# PIC32_WIZ810MJ.net
KiCad netlist of a schematic drawn in EAGLE
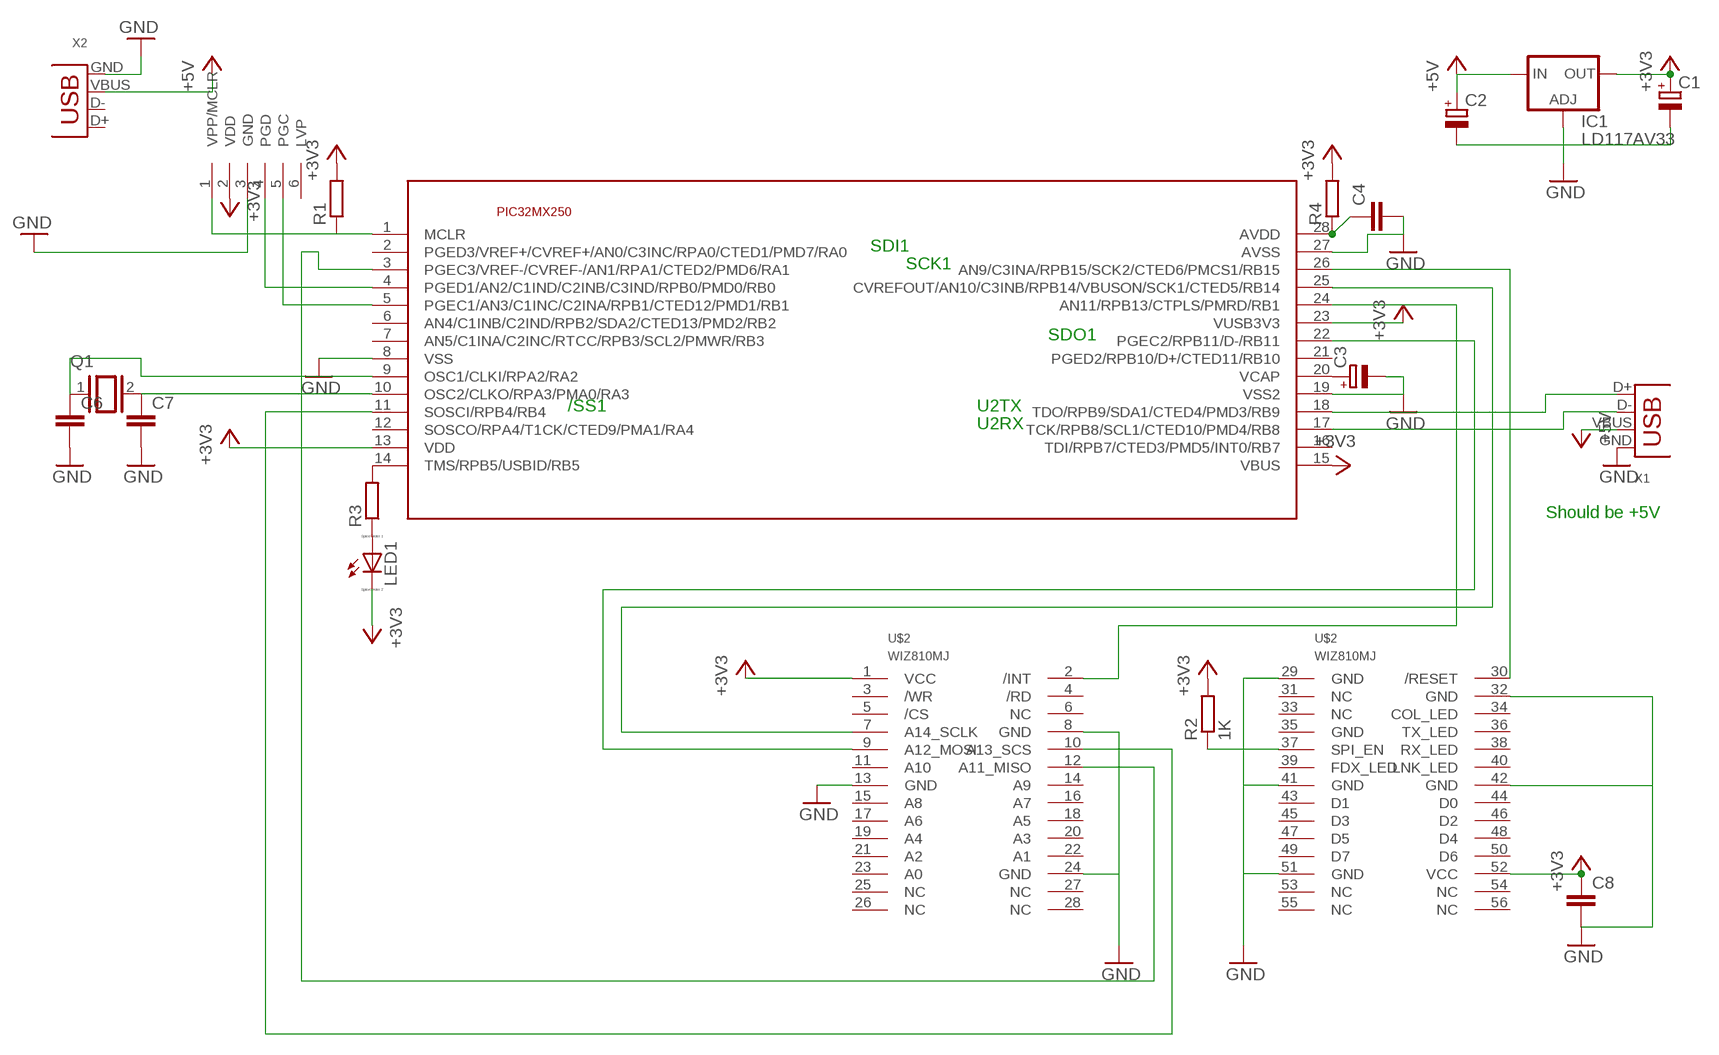
[diagram p0: schematic, sheet 1]

(export (version "E")
  (design (tool "Eeschema 10.0.6"))
  (components
    (comp (ref "C1")
      (value "CPOL-EUE3.5-10")
      (footprint "eagle-import:E3,5-10")
      (libsource (lib "eagle-import") (part "CPOL-EUE3.5-10"))
    )
    (comp (ref "C2")
      (value "CPOL-EUE3.5-10")
      (footprint "eagle-import:E3,5-10")
      (libsource (lib "eagle-import") (part "CPOL-EUE3.5-10"))
    )
    (comp (ref "C3")
      (value "CPOL-EUE2.5-6")
      (footprint "eagle-import:E2,5-6")
      (libsource (lib "eagle-import") (part "CPOL-EUE2.5-6"))
    )
    (comp (ref "C4")
      (value "C-EU050-055X075")
      (footprint "eagle-import:C050-055X075")
      (libsource (lib "eagle-import") (part "C-EU050-055X075"))
    )
    (comp (ref "C6")
      (value "C-EU025-025X050")
      (footprint "eagle-import:C025-025X050")
      (libsource (lib "eagle-import") (part "C-EU025-025X050"))
    )
    (comp (ref "C7")
      (value "C-EU025-025X050")
      (footprint "eagle-import:C025-025X050")
      (libsource (lib "eagle-import") (part "C-EU025-025X050"))
    )
    (comp (ref "C8")
      (value "C-EU050-055X075")
      (footprint "eagle-import:C050-055X075")
      (libsource (lib "eagle-import") (part "C-EU050-055X075"))
    )
    (comp (ref "IC1")
      (value "LD117AV33")
      (footprint "eagle-import:TO220L1")
      (libsource (lib "eagle-import") (part "LD117A?V33"))
    )
    (comp (ref "LED1")
      (value "LED_ELD260")
      (footprint "eagle-import:LED_LD260")
      (libsource (lib "eagle-import") (part "LED_ELD260"))
    )
    (comp (ref "Q1")
      (value "XTAL/S")
      (footprint "eagle-import:QS")
      (libsource (lib "eagle-import") (part "XTAL/S"))
    )
    (comp (ref "R1")
      (value "R-EU_0204/5")
      (footprint "eagle-import:0204_5")
      (libsource (lib "eagle-import") (part "R-EU_0204/5"))
    )
    (comp (ref "R2")
      (value "1K")
      (footprint "eagle-import:0204_5")
      (libsource (lib "eagle-import") (part "R-EU_0204/5"))
    )
    (comp (ref "R3")
      (value "R-EU_0204/5")
      (footprint "eagle-import:0204_5")
      (libsource (lib "eagle-import") (part "R-EU_0204/5"))
    )
    (comp (ref "R4")
      (value "R-EU_0204/5")
      (footprint "eagle-import:0204_5")
      (libsource (lib "eagle-import") (part "R-EU_0204/5"))
    )
    (comp (ref "U$1")
      (value "PIC32MX2XXDIP28_SLIM")
      (footprint "eagle-import:DIP254P762X508-28")
      (libsource (lib "eagle-import") (part "PIC32MX2XXDIP28_SLIM"))
    )
    (comp (ref "U$2")
      (value "WIZ810MJ")
      (footprint "eagle-import:WIZ810MJ")
      (libsource (lib "eagle-import") (part "WIZ810MJ"))
    )
    (comp (ref "U$3")
      (value "ICSP-6_6P")
      (footprint "eagle-import:1X06-CLEANBIG")
      (libsource (lib "eagle-import") (part "ICSP-6_6P"))
    )
    (comp (ref "X1")
      (value "USB-A-H")
      (footprint "eagle-import:USB-A-H")
      (libsource (lib "eagle-import") (part "USB-A-H"))
    )
    (comp (ref "X2")
      (value "USB-B-H")
      (footprint "eagle-import:USB-B-H")
      (libsource (lib "eagle-import") (part "USB-B-H"))
    )
  )
  (nets
    (net (code "1") (name "+3V3") (class "Default")
      (node (ref "C1") (pin "+") (pinfunction "+_+") (pintype "passive"))
      (node (ref "C8") (pin "1") (pinfunction "1_1") (pintype "passive"))
      (node (ref "IC1") (pin "2") (pinfunction "OUT_2") (pintype "passive"))
      (node (ref "LED1") (pin "K") (pinfunction "C_K") (pintype "passive"))
      (node (ref "R1") (pin "2") (pinfunction "2_2") (pintype "passive"))
      (node (ref "R2") (pin "2") (pinfunction "2_2") (pintype "passive"))
      (node (ref "R4") (pin "2") (pinfunction "2_2") (pintype "passive"))
      (node (ref "U$1") (pin "13") (pinfunction "VDD_13") (pintype "power_in"))
      (node (ref "U$1") (pin "15") (pinfunction "VBUS_15") (pintype "bidirectional"))
      (node (ref "U$1") (pin "23") (pinfunction "VUSB3V3_23") (pintype "bidirectional"))
      (node (ref "U$2") (pin "1") (pinfunction "VCC_1") (pintype "bidirectional"))
      (node (ref "U$2") (pin "52") (pinfunction "VCC_52") (pintype "bidirectional"))
      (node (ref "U$3") (pin "2") (pinfunction "VDD_2") (pintype "bidirectional"))
    )
    (net (code "2") (name "+5V") (class "Default")
      (node (ref "C2") (pin "+") (pinfunction "+_+") (pintype "passive"))
      (node (ref "IC1") (pin "3") (pinfunction "IN_3") (pintype "input"))
      (node (ref "X1") (pin "VBUS") (pinfunction "VBUS_VBUS") (pintype "bidirectional"))
      (node (ref "X2") (pin "VBUS") (pinfunction "VBUS_VBUS") (pintype "bidirectional"))
    )
    (net (code "3") (name "GND") (class "Default")
      (node (ref "C1") (pin "-") (pinfunction "-_-") (pintype "passive"))
      (node (ref "C2") (pin "-") (pinfunction "-_-") (pintype "passive"))
      (node (ref "C3") (pin "-") (pinfunction "-_-") (pintype "passive"))
      (node (ref "C4") (pin "2") (pinfunction "2_2") (pintype "passive"))
      (node (ref "C6") (pin "2") (pinfunction "2_2") (pintype "passive"))
      (node (ref "C7") (pin "2") (pinfunction "2_2") (pintype "passive"))
      (node (ref "C8") (pin "2") (pinfunction "2_2") (pintype "passive"))
      (node (ref "IC1") (pin "1") (pinfunction "ADJ_1") (pintype "input"))
      (node (ref "U$1") (pin "19") (pinfunction "VSS2_19") (pintype "bidirectional"))
      (node (ref "U$1") (pin "27") (pinfunction "AVSS_27") (pintype "bidirectional"))
      (node (ref "U$1") (pin "8") (pinfunction "VSS_8") (pintype "power_in"))
      (node (ref "U$2") (pin "13") (pinfunction "GND_13") (pintype "bidirectional"))
      (node (ref "U$2") (pin "24") (pinfunction "GND_24") (pintype "bidirectional"))
      (node (ref "U$2") (pin "29") (pinfunction "GND_29") (pintype "bidirectional"))
      (node (ref "U$2") (pin "32") (pinfunction "GND_32") (pintype "bidirectional"))
      (node (ref "U$2") (pin "41") (pinfunction "GND_41") (pintype "bidirectional"))
      (node (ref "U$2") (pin "42") (pinfunction "GND_42") (pintype "bidirectional"))
      (node (ref "U$2") (pin "51") (pinfunction "GND_51") (pintype "bidirectional"))
      (node (ref "U$2") (pin "8") (pinfunction "GND_8") (pintype "bidirectional"))
      (node (ref "U$3") (pin "3") (pinfunction "GND_3") (pintype "bidirectional"))
      (node (ref "X1") (pin "GND") (pinfunction "GND_GND") (pintype "bidirectional"))
      (node (ref "X2") (pin "GND") (pinfunction "GND_GND") (pintype "bidirectional"))
    )
    (net (code "4") (name "Net-(LED1-PadA)") (class "Default")
      (node (ref "LED1") (pin "A") (pinfunction "A_A") (pintype "passive"))
      (node (ref "R3") (pin "1") (pinfunction "1_1") (pintype "passive"))
    )
    (net (code "5") (name "Net-(U$1-AN9{slash}C3INA{slash}RPB15{slash}SCK2{slash}CTED6{slash}PMCS1{slash}RB15)") (class "Default")
      (node (ref "U$1") (pin "26") (pinfunction "AN9/C3INA/RPB15/SCK2/CTED6/PMCS1/RB15_26") (pintype "bidirectional"))
      (node (ref "U$2") (pin "30") (pinfunction "/RESET_30") (pintype "bidirectional"))
    )
    (net (code "6") (name "Net-(U$1-AN11{slash}RPB13{slash}CTPLS{slash}PMRD{slash}RB1)") (class "Default")
      (node (ref "U$1") (pin "24") (pinfunction "AN11/RPB13/CTPLS/PMRD/RB1_24") (pintype "bidirectional"))
      (node (ref "U$2") (pin "2") (pinfunction "/INT_2") (pintype "bidirectional"))
    )
    (net (code "7") (name "Net-(U$1-AVDD)") (class "Default")
      (node (ref "C4") (pin "1") (pinfunction "1_1") (pintype "passive"))
      (node (ref "R4") (pin "1") (pinfunction "1_1") (pintype "passive"))
      (node (ref "U$1") (pin "28") (pinfunction "AVDD_28") (pintype "bidirectional"))
    )
    (net (code "8") (name "Net-(U$1-CVREFOUT{slash}AN10{slash}C3INB{slash}RPB14{slash}VBUSON{slash}SCK1{slash}CTED5{slash}RB14)") (class "Default")
      (node (ref "U$1") (pin "25") (pinfunction "CVREFOUT/AN10/C3INB/RPB14/VBUSON/SCK1/CTED5/RB14_25") (pintype "bidirectional"))
      (node (ref "U$2") (pin "7") (pinfunction "A14_SCLK_7") (pintype "bidirectional"))
    )
    (net (code "9") (name "Net-(U$1-MCLR)") (class "Default")
      (node (ref "R1") (pin "1") (pinfunction "1_1") (pintype "passive"))
      (node (ref "U$1") (pin "1") (pinfunction "MCLR_1") (pintype "bidirectional"))
      (node (ref "U$3") (pin "1") (pinfunction "VPP/MCLR_1") (pintype "bidirectional"))
    )
    (net (code "10") (name "Net-(U$1-OSC1{slash}CLKI{slash}RPA2{slash}RA2)") (class "Default")
      (node (ref "C6") (pin "1") (pinfunction "1_1") (pintype "passive"))
      (node (ref "Q1") (pin "1") (pinfunction "1_1") (pintype "passive"))
      (node (ref "U$1") (pin "9") (pinfunction "OSC1/CLKI/RPA2/RA2_9") (pintype "bidirectional"))
    )
    (net (code "11") (name "Net-(U$1-OSC2{slash}CLKO{slash}RPA3{slash}PMA0{slash}RA3)") (class "Default")
      (node (ref "C7") (pin "1") (pinfunction "1_1") (pintype "passive"))
      (node (ref "Q1") (pin "2") (pinfunction "2_2") (pintype "passive"))
      (node (ref "U$1") (pin "10") (pinfunction "OSC2/CLKO/RPA3/PMA0/RA3_10") (pintype "bidirectional"))
    )
    (net (code "12") (name "Net-(U$1-PGEC1{slash}AN3{slash}C1INC{slash}C2INA{slash}RPB1{slash}CTED12{slash}PMD1{slash}RB1)") (class "Default")
      (node (ref "U$1") (pin "5") (pinfunction "PGEC1/AN3/C1INC/C2INA/RPB1/CTED12/PMD1/RB1_5") (pintype "bidirectional"))
      (node (ref "U$3") (pin "5") (pinfunction "PGC_5") (pintype "bidirectional"))
    )
    (net (code "13") (name "Net-(U$1-PGEC2{slash}RPB11{slash}D-{slash}RB11)") (class "Default")
      (node (ref "U$1") (pin "22") (pinfunction "PGEC2/RPB11/D-/RB11_22") (pintype "bidirectional"))
      (node (ref "U$2") (pin "9") (pinfunction "A12_MOSI_9") (pintype "bidirectional"))
    )
    (net (code "14") (name "Net-(U$1-PGEC3{slash}VREF-{slash}CVREF-{slash}AN1{slash}RPA1{slash}CTED2{slash}PMD6{slash}RA1)") (class "Default")
      (node (ref "U$1") (pin "3") (pinfunction "PGEC3/VREF-/CVREF-/AN1/RPA1/CTED2/PMD6/RA1_3") (pintype "bidirectional"))
      (node (ref "U$2") (pin "12") (pinfunction "A11_MISO_12") (pintype "bidirectional"))
    )
    (net (code "15") (name "Net-(U$1-PGED1{slash}AN2{slash}C1IND{slash}C2INB{slash}C3IND{slash}RPB0{slash}PMD0{slash}RB0)") (class "Default")
      (node (ref "U$1") (pin "4") (pinfunction "PGED1/AN2/C1IND/C2INB/C3IND/RPB0/PMD0/RB0_4") (pintype "bidirectional"))
      (node (ref "U$3") (pin "4") (pinfunction "PGD_4") (pintype "bidirectional"))
    )
    (net (code "16") (name "Net-(U$1-SOSCI{slash}RPB4{slash}RB4)") (class "Default")
      (node (ref "U$1") (pin "11") (pinfunction "SOSCI/RPB4/RB4_11") (pintype "bidirectional"))
      (node (ref "U$2") (pin "10") (pinfunction "A13_SCS_10") (pintype "bidirectional"))
    )
    (net (code "17") (name "Net-(U$1-TCK{slash}RPB8{slash}SCL1{slash}CTED10{slash}PMD4{slash}RB8)") (class "Default")
      (node (ref "U$1") (pin "17") (pinfunction "TCK/RPB8/SCL1/CTED10/PMD4/RB8_17") (pintype "bidirectional"))
      (node (ref "X1") (pin "D-") (pinfunction "D-_D-") (pintype "bidirectional"))
    )
    (net (code "18") (name "Net-(U$1-TDO{slash}RPB9{slash}SDA1{slash}CTED4{slash}PMD3{slash}RB9)") (class "Default")
      (node (ref "U$1") (pin "18") (pinfunction "TDO/RPB9/SDA1/CTED4/PMD3/RB9_18") (pintype "bidirectional"))
      (node (ref "X1") (pin "D+") (pinfunction "D+_D+") (pintype "bidirectional"))
    )
    (net (code "19") (name "Net-(U$1-TMS{slash}RPB5{slash}USBID{slash}RB5)") (class "Default")
      (node (ref "R3") (pin "2") (pinfunction "2_2") (pintype "passive"))
      (node (ref "U$1") (pin "14") (pinfunction "TMS/RPB5/USBID/RB5_14") (pintype "bidirectional"))
    )
    (net (code "20") (name "Net-(U$1-VCAP)") (class "Default")
      (node (ref "C3") (pin "+") (pinfunction "+_+") (pintype "passive"))
      (node (ref "U$1") (pin "20") (pinfunction "VCAP_20") (pintype "bidirectional"))
    )
    (net (code "21") (name "Net-(U$2-SPI_EN)") (class "Default")
      (node (ref "R2") (pin "1") (pinfunction "1_1") (pintype "passive"))
      (node (ref "U$2") (pin "37") (pinfunction "SPI_EN_37") (pintype "bidirectional"))
    )
    (net (code "22") (name "unconnected-(U$1-AN4{slash}C1INB{slash}C2IND{slash}RPB2{slash}SDA2{slash}CTED13{slash}PMD2{slash}RB2-Pad6)") (class "Default")
      (node (ref "U$1") (pin "6") (pinfunction "AN4/C1INB/C2IND/RPB2/SDA2/CTED13/PMD2/RB2_6") (pintype "bidirectional"))
    )
    (net (code "23") (name "unconnected-(U$1-AN5{slash}C1INA{slash}C2INC{slash}RTCC{slash}RPB3{slash}SCL2{slash}PMWR{slash}RB3-Pad7)") (class "Default")
      (node (ref "U$1") (pin "7") (pinfunction "AN5/C1INA/C2INC/RTCC/RPB3/SCL2/PMWR/RB3_7") (pintype "bidirectional"))
    )
    (net (code "24") (name "unconnected-(U$1-PGED2{slash}RPB10{slash}D+{slash}CTED11{slash}RB10-Pad21)") (class "Default")
      (node (ref "U$1") (pin "21") (pinfunction "PGED2/RPB10/D+/CTED11/RB10_21") (pintype "bidirectional"))
    )
    (net (code "25") (name "unconnected-(U$1-PGED3{slash}VREF+{slash}CVREF+{slash}AN0{slash}C3INC{slash}RPA0{slash}CTED1{slash}PMD7{slash}RA0-Pad2)") (class "Default")
      (node (ref "U$1") (pin "2") (pinfunction "PGED3/VREF+/CVREF+/AN0/C3INC/RPA0/CTED1/PMD7/RA0_2") (pintype "bidirectional"))
    )
    (net (code "26") (name "unconnected-(U$1-SOSCO{slash}RPA4{slash}T1CK{slash}CTED9{slash}PMA1{slash}RA4-Pad12)") (class "Default")
      (node (ref "U$1") (pin "12") (pinfunction "SOSCO/RPA4/T1CK/CTED9/PMA1/RA4_12") (pintype "bidirectional"))
    )
    (net (code "27") (name "unconnected-(U$1-TDI{slash}RPB7{slash}CTED3{slash}PMD5{slash}INT0{slash}RB7-Pad16)") (class "Default")
      (node (ref "U$1") (pin "16") (pinfunction "TDI/RPB7/CTED3/PMD5/INT0/RB7_16") (pintype "bidirectional"))
    )
    (net (code "28") (name "unconnected-(U$2-A0-Pad23)") (class "Default")
      (node (ref "U$2") (pin "23") (pinfunction "A0_23") (pintype "bidirectional"))
    )
    (net (code "29") (name "unconnected-(U$2-A1-Pad22)") (class "Default")
      (node (ref "U$2") (pin "22") (pinfunction "A1_22") (pintype "bidirectional"))
    )
    (net (code "30") (name "unconnected-(U$2-A2-Pad21)") (class "Default")
      (node (ref "U$2") (pin "21") (pinfunction "A2_21") (pintype "bidirectional"))
    )
    (net (code "31") (name "unconnected-(U$2-A3-Pad20)") (class "Default")
      (node (ref "U$2") (pin "20") (pinfunction "A3_20") (pintype "bidirectional"))
    )
    (net (code "32") (name "unconnected-(U$2-A4-Pad19)") (class "Default")
      (node (ref "U$2") (pin "19") (pinfunction "A4_19") (pintype "bidirectional"))
    )
    (net (code "33") (name "unconnected-(U$2-A5-Pad18)") (class "Default")
      (node (ref "U$2") (pin "18") (pinfunction "A5_18") (pintype "bidirectional"))
    )
    (net (code "34") (name "unconnected-(U$2-A6-Pad17)") (class "Default")
      (node (ref "U$2") (pin "17") (pinfunction "A6_17") (pintype "bidirectional"))
    )
    (net (code "35") (name "unconnected-(U$2-A7-Pad16)") (class "Default")
      (node (ref "U$2") (pin "16") (pinfunction "A7_16") (pintype "bidirectional"))
    )
    (net (code "36") (name "unconnected-(U$2-A8-Pad15)") (class "Default")
      (node (ref "U$2") (pin "15") (pinfunction "A8_15") (pintype "bidirectional"))
    )
    (net (code "37") (name "unconnected-(U$2-A9-Pad14)") (class "Default")
      (node (ref "U$2") (pin "14") (pinfunction "A9_14") (pintype "bidirectional"))
    )
    (net (code "38") (name "unconnected-(U$2-A10-Pad11)") (class "Default")
      (node (ref "U$2") (pin "11") (pinfunction "A10_11") (pintype "bidirectional"))
    )
    (net (code "39") (name "unconnected-(U$2-COL_LED-Pad34)") (class "Default")
      (node (ref "U$2") (pin "34") (pinfunction "COL_LED_34") (pintype "bidirectional"))
    )
    (net (code "40") (name "unconnected-(U$2-D0-Pad44)") (class "Default")
      (node (ref "U$2") (pin "44") (pinfunction "D0_44") (pintype "bidirectional"))
    )
    (net (code "41") (name "unconnected-(U$2-D1-Pad43)") (class "Default")
      (node (ref "U$2") (pin "43") (pinfunction "D1_43") (pintype "bidirectional"))
    )
    (net (code "42") (name "unconnected-(U$2-D2-Pad46)") (class "Default")
      (node (ref "U$2") (pin "46") (pinfunction "D2_46") (pintype "bidirectional"))
    )
    (net (code "43") (name "unconnected-(U$2-D3-Pad45)") (class "Default")
      (node (ref "U$2") (pin "45") (pinfunction "D3_45") (pintype "bidirectional"))
    )
    (net (code "44") (name "unconnected-(U$2-D4-Pad48)") (class "Default")
      (node (ref "U$2") (pin "48") (pinfunction "D4_48") (pintype "bidirectional"))
    )
    (net (code "45") (name "unconnected-(U$2-D5-Pad47)") (class "Default")
      (node (ref "U$2") (pin "47") (pinfunction "D5_47") (pintype "bidirectional"))
    )
    (net (code "46") (name "unconnected-(U$2-D6-Pad50)") (class "Default")
      (node (ref "U$2") (pin "50") (pinfunction "D6_50") (pintype "bidirectional"))
    )
    (net (code "47") (name "unconnected-(U$2-D7-Pad49)") (class "Default")
      (node (ref "U$2") (pin "49") (pinfunction "D7_49") (pintype "bidirectional"))
    )
    (net (code "48") (name "unconnected-(U$2-FDX_LED-Pad39)") (class "Default")
      (node (ref "U$2") (pin "39") (pinfunction "FDX_LED_39") (pintype "bidirectional"))
    )
    (net (code "49") (name "unconnected-(U$2-GND-Pad35)") (class "Default")
      (node (ref "U$2") (pin "35") (pinfunction "GND_35") (pintype "bidirectional"))
    )
    (net (code "50") (name "unconnected-(U$2-LNK_LED-Pad40)") (class "Default")
      (node (ref "U$2") (pin "40") (pinfunction "LNK_LED_40") (pintype "bidirectional"))
    )
    (net (code "51") (name "unconnected-(U$2-NC-Pad6)") (class "Default")
      (node (ref "U$2") (pin "6") (pinfunction "NC_6") (pintype "bidirectional"))
    )
    (net (code "52") (name "unconnected-(U$2-NC-Pad25)") (class "Default")
      (node (ref "U$2") (pin "25") (pinfunction "NC_25") (pintype "bidirectional"))
    )
    (net (code "53") (name "unconnected-(U$2-NC-Pad26)") (class "Default")
      (node (ref "U$2") (pin "26") (pinfunction "NC_26") (pintype "bidirectional"))
    )
    (net (code "54") (name "unconnected-(U$2-NC-Pad27)") (class "Default")
      (node (ref "U$2") (pin "27") (pinfunction "NC_27") (pintype "bidirectional"))
    )
    (net (code "55") (name "unconnected-(U$2-NC-Pad28)") (class "Default")
      (node (ref "U$2") (pin "28") (pinfunction "NC_28") (pintype "bidirectional"))
    )
    (net (code "56") (name "unconnected-(U$2-NC-Pad31)") (class "Default")
      (node (ref "U$2") (pin "31") (pinfunction "NC_31") (pintype "bidirectional"))
    )
    (net (code "57") (name "unconnected-(U$2-NC-Pad33)") (class "Default")
      (node (ref "U$2") (pin "33") (pinfunction "NC_33") (pintype "bidirectional"))
    )
    (net (code "58") (name "unconnected-(U$2-NC-Pad53)") (class "Default")
      (node (ref "U$2") (pin "53") (pinfunction "NC_53") (pintype "bidirectional"))
    )
    (net (code "59") (name "unconnected-(U$2-NC-Pad54)") (class "Default")
      (node (ref "U$2") (pin "54") (pinfunction "NC_54") (pintype "bidirectional"))
    )
    (net (code "60") (name "unconnected-(U$2-NC-Pad55)") (class "Default")
      (node (ref "U$2") (pin "55") (pinfunction "NC_55") (pintype "bidirectional"))
    )
    (net (code "61") (name "unconnected-(U$2-NC-Pad56)") (class "Default")
      (node (ref "U$2") (pin "56") (pinfunction "NC_56") (pintype "bidirectional"))
    )
    (net (code "62") (name "unconnected-(U$2-RX_LED-Pad38)") (class "Default")
      (node (ref "U$2") (pin "38") (pinfunction "RX_LED_38") (pintype "bidirectional"))
    )
    (net (code "63") (name "unconnected-(U$2-TX_LED-Pad36)") (class "Default")
      (node (ref "U$2") (pin "36") (pinfunction "TX_LED_36") (pintype "bidirectional"))
    )
    (net (code "64") (name "unconnected-(U$2-{slash}CS-Pad5)") (class "Default")
      (node (ref "U$2") (pin "5") (pinfunction "/CS_5") (pintype "bidirectional"))
    )
    (net (code "65") (name "unconnected-(U$2-{slash}RD-Pad4)") (class "Default")
      (node (ref "U$2") (pin "4") (pinfunction "/RD_4") (pintype "bidirectional"))
    )
    (net (code "66") (name "unconnected-(U$2-{slash}WR-Pad3)") (class "Default")
      (node (ref "U$2") (pin "3") (pinfunction "/WR_3") (pintype "bidirectional"))
    )
    (net (code "67") (name "unconnected-(U$3-LVP-Pad6)") (class "Default")
      (node (ref "U$3") (pin "6") (pinfunction "LVP_6") (pintype "bidirectional"))
    )
    (net (code "68") (name "unconnected-(X2-PadD+)") (class "Default")
      (node (ref "X2") (pin "D+") (pinfunction "D+_D+") (pintype "bidirectional"))
    )
    (net (code "69") (name "unconnected-(X2-PadD-)") (class "Default")
      (node (ref "X2") (pin "D-") (pinfunction "D-_D-") (pintype "bidirectional"))
    )
  )
)
